# mbeduino010_eagle6.net
KiCad netlist of a schematic drawn in EAGLE
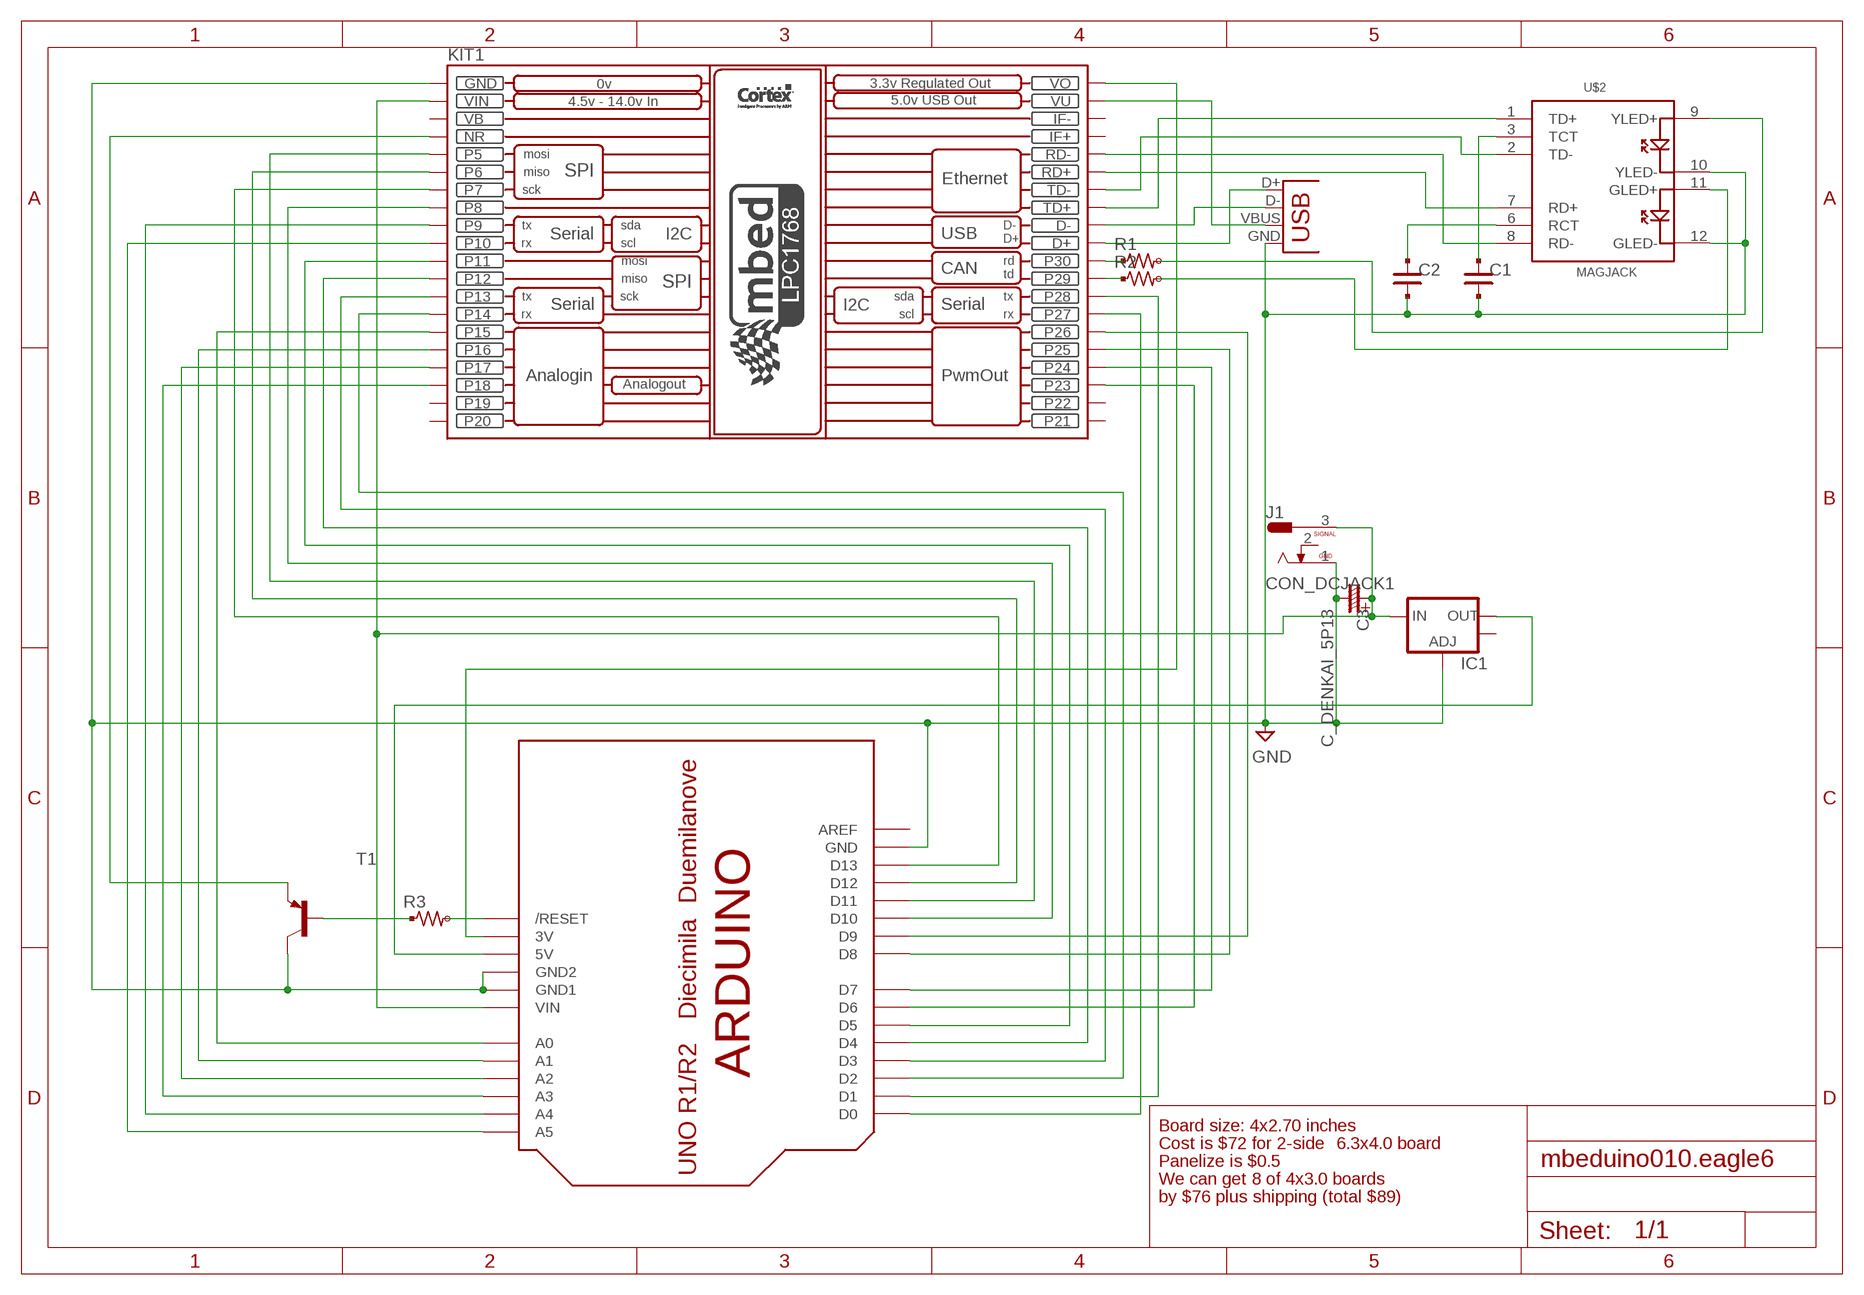
[diagram p0: schematic, sheet 1]

(export (version "E")
  (design (tool "Eeschema 10.0.6"))
  (components
    (comp (ref "C1")
      (value "C_PAD_PAD_2125")
      (footprint "eagle-import:CR_2125")
      (libsource (lib "eagle-import") (part "C_PAD_PAD_2125"))
    )
    (comp (ref "C2")
      (value "C_PAD_PAD_2125")
      (footprint "eagle-import:CR_2125")
      (libsource (lib "eagle-import") (part "C_PAD_PAD_2125"))
    )
    (comp (ref "C3")
      (value "C_DENKAI_5P13")
      (footprint "eagle-import:C_2.5PHI6")
      (libsource (lib "eagle-import") (part "C_DENKAI_2.5P6"))
    )
    (comp (ref "IC1")
      (value "V_REG_LM1117SOT223")
      (footprint "eagle-import:SOT223")
      (libsource (lib "eagle-import") (part "V_REG_LM1117SOT223"))
    )
    (comp (ref "J1")
      (value "CON_DCJACK1")
      (footprint "eagle-import:CON_DCJACK")
      (libsource (lib "eagle-import") (part "CON_DCJACK1"))
    )
    (comp (ref "KIT1")
      (value "MBED_NXP_LPC1768")
      (footprint "eagle-import:MBED-KIT")
      (libsource (lib "eagle-import") (part "MBED_NXP_LPC1768"))
    )
    (comp (ref "R1")
      (value "R_US_PAD_VIA_2125")
      (footprint "eagle-import:R_2125_PADVIA")
      (libsource (lib "eagle-import") (part "R_US_PAD_VIA_2125"))
    )
    (comp (ref "R2")
      (value "R_US_PAD_VIA_2125")
      (footprint "eagle-import:R_2125_PADVIA")
      (libsource (lib "eagle-import") (part "R_US_PAD_VIA_2125"))
    )
    (comp (ref "R3")
      (value "R_US_PAD_VIA_2125")
      (footprint "eagle-import:R_2125_PADVIA")
      (libsource (lib "eagle-import") (part "R_US_PAD_VIA_2125"))
    )
    (comp (ref "T1")
      (value "-PNP-SOT23-BCE")
      (footprint "eagle-import:SOT23-BCE")
      (libsource (lib "eagle-import") (part "-PNP-SOT23-BCE"))
    )
    (comp (ref "U$1")
      (value "ARDUINO-NOHOLE")
      (footprint "eagle-import:ARDUINO-NOHOLE")
      (libsource (lib "eagle-import") (part "ARDUINO-NOHOLE"))
    )
    (comp (ref "U$2")
      (value "MAGJACK")
      (footprint "eagle-import:MAGJACK")
      (libsource (lib "eagle-import") (part "MAGJACK"))
    )
    (comp (ref "X1")
      (value "USB-A-S")
      (footprint "eagle-import:USB-A-S")
      (libsource (lib "eagle-import") (part "USB-A-S"))
    )
  )
  (nets
    (net (code "1") (name "/VB") (class "Default")
      (node (ref "KIT1") (pin "VB") (pinfunction "VB_VB") (pintype "power_in"))
    )
    (net (code "2") (name "GND") (class "Default")
      (node (ref "C1") (pin "2") (pinfunction "2_2") (pintype "passive"))
      (node (ref "C2") (pin "2") (pinfunction "2_2") (pintype "passive"))
      (node (ref "C3") (pin "-") (pinfunction "-_-") (pintype "passive"))
      (node (ref "IC1") (pin "1") (pinfunction "ADJ_1") (pintype "input"))
      (node (ref "J1") (pin "1") (pinfunction "3_1") (pintype "passive"))
      (node (ref "KIT1") (pin "GND") (pinfunction "GND_GND") (pintype "power_in"))
      (node (ref "T1") (pin "C") (pinfunction "C_C") (pintype "passive"))
      (node (ref "U$1") (pin "GND") (pinfunction "GND_GND") (pintype "power_in"))
      (node (ref "U$1") (pin "GND1") (pinfunction "GND1_GND1") (pintype "power_in"))
      (node (ref "U$1") (pin "GND2") (pinfunction "GND2_GND2") (pintype "power_in"))
      (node (ref "U$2") (pin "10") (pinfunction "YLED-_10") (pintype "bidirectional"))
      (node (ref "U$2") (pin "12") (pinfunction "GLED-_12") (pintype "bidirectional"))
      (node (ref "X1") (pin "GND") (pinfunction "GND_GND") (pintype "bidirectional"))
    )
    (net (code "3") (name "Net-(IC1-IN)") (class "Default")
      (node (ref "C3") (pin "+") (pinfunction "+_+") (pintype "passive"))
      (node (ref "IC1") (pin "3") (pinfunction "IN_3") (pintype "input"))
      (node (ref "J1") (pin "3") (pinfunction "1_3") (pintype "passive"))
      (node (ref "KIT1") (pin "VIN") (pinfunction "VIN_VIN") (pintype "power_in"))
      (node (ref "U$1") (pin "VIN") (pinfunction "VIN_VIN") (pintype "power_in"))
    )
    (net (code "4") (name "Net-(IC1-OUT-Pad2)") (class "Default")
      (node (ref "IC1") (pin "2") (pinfunction "OUT_2") (pintype "output"))
      (node (ref "U$1") (pin "5V") (pinfunction "5V_5V") (pintype "power_in"))
    )
    (net (code "5") (name "Net-(KIT1-P5)") (class "Default")
      (node (ref "KIT1") (pin "P$5") (pinfunction "P5_P$5") (pintype "bidirectional"))
      (node (ref "U$1") (pin "D11") (pinfunction "D11_D11") (pintype "bidirectional"))
    )
    (net (code "6") (name "Net-(KIT1-P6)") (class "Default")
      (node (ref "KIT1") (pin "P$6") (pinfunction "P6_P$6") (pintype "bidirectional"))
      (node (ref "U$1") (pin "D12") (pinfunction "D12_D12") (pintype "bidirectional"))
    )
    (net (code "7") (name "Net-(KIT1-P7)") (class "Default")
      (node (ref "KIT1") (pin "P$7") (pinfunction "P7_P$7") (pintype "bidirectional"))
      (node (ref "U$1") (pin "D13") (pinfunction "D13_D13") (pintype "bidirectional"))
    )
    (net (code "8") (name "Net-(KIT1-P8)") (class "Default")
      (node (ref "KIT1") (pin "P$8") (pinfunction "P8_P$8") (pintype "bidirectional"))
      (node (ref "U$1") (pin "D10") (pinfunction "D10_D10") (pintype "bidirectional"))
    )
    (net (code "9") (name "Net-(KIT1-P9)") (class "Default")
      (node (ref "KIT1") (pin "P$9") (pinfunction "P9_P$9") (pintype "bidirectional"))
      (node (ref "U$1") (pin "A4") (pinfunction "A4_A4") (pintype "bidirectional"))
    )
    (net (code "10") (name "Net-(KIT1-P10)") (class "Default")
      (node (ref "KIT1") (pin "P$10") (pinfunction "P10_P$10") (pintype "bidirectional"))
      (node (ref "U$1") (pin "A5") (pinfunction "A5_A5") (pintype "bidirectional"))
    )
    (net (code "11") (name "Net-(KIT1-P11)") (class "Default")
      (node (ref "KIT1") (pin "P$11") (pinfunction "P11_P$11") (pintype "bidirectional"))
      (node (ref "U$1") (pin "D5") (pinfunction "D5_D5") (pintype "bidirectional"))
    )
    (net (code "12") (name "Net-(KIT1-P12)") (class "Default")
      (node (ref "KIT1") (pin "P$12") (pinfunction "P12_P$12") (pintype "bidirectional"))
      (node (ref "U$1") (pin "D4") (pinfunction "D4_D4") (pintype "bidirectional"))
    )
    (net (code "13") (name "Net-(KIT1-P13)") (class "Default")
      (node (ref "KIT1") (pin "P$13") (pinfunction "P13_P$13") (pintype "bidirectional"))
      (node (ref "U$1") (pin "D3") (pinfunction "D3_D3") (pintype "bidirectional"))
    )
    (net (code "14") (name "Net-(KIT1-P14)") (class "Default")
      (node (ref "KIT1") (pin "P$14") (pinfunction "P14_P$14") (pintype "bidirectional"))
      (node (ref "U$1") (pin "D2") (pinfunction "D2_D2") (pintype "bidirectional"))
    )
    (net (code "15") (name "Net-(KIT1-P15)") (class "Default")
      (node (ref "KIT1") (pin "P$15") (pinfunction "P15_P$15") (pintype "bidirectional"))
      (node (ref "U$1") (pin "A0") (pinfunction "A0_A0") (pintype "bidirectional"))
    )
    (net (code "16") (name "Net-(KIT1-P16)") (class "Default")
      (node (ref "KIT1") (pin "P$16") (pinfunction "P16_P$16") (pintype "bidirectional"))
      (node (ref "U$1") (pin "A1") (pinfunction "A1_A1") (pintype "bidirectional"))
    )
    (net (code "17") (name "Net-(KIT1-P17)") (class "Default")
      (node (ref "KIT1") (pin "P$17") (pinfunction "P17_P$17") (pintype "bidirectional"))
      (node (ref "U$1") (pin "A2") (pinfunction "A2_A2") (pintype "bidirectional"))
    )
    (net (code "18") (name "Net-(KIT1-P18)") (class "Default")
      (node (ref "KIT1") (pin "P$18") (pinfunction "P18_P$18") (pintype "bidirectional"))
      (node (ref "U$1") (pin "A3") (pinfunction "A3_A3") (pintype "bidirectional"))
    )
    (net (code "19") (name "Net-(KIT1-P23)") (class "Default")
      (node (ref "KIT1") (pin "P$23") (pinfunction "P23_P$23") (pintype "bidirectional"))
      (node (ref "U$1") (pin "D6") (pinfunction "D6_D6") (pintype "bidirectional"))
    )
    (net (code "20") (name "Net-(KIT1-P24)") (class "Default")
      (node (ref "KIT1") (pin "P$24") (pinfunction "P24_P$24") (pintype "bidirectional"))
      (node (ref "U$1") (pin "D7") (pinfunction "D7_D7") (pintype "bidirectional"))
    )
    (net (code "21") (name "Net-(KIT1-P25)") (class "Default")
      (node (ref "KIT1") (pin "P$25") (pinfunction "P25_P$25") (pintype "bidirectional"))
      (node (ref "U$1") (pin "D8") (pinfunction "D8_D8") (pintype "bidirectional"))
    )
    (net (code "22") (name "Net-(KIT1-P26)") (class "Default")
      (node (ref "KIT1") (pin "P$26") (pinfunction "P26_P$26") (pintype "bidirectional"))
      (node (ref "U$1") (pin "D9") (pinfunction "D9_D9") (pintype "bidirectional"))
    )
    (net (code "23") (name "Net-(KIT1-P27)") (class "Default")
      (node (ref "KIT1") (pin "P$27") (pinfunction "P27_P$27") (pintype "bidirectional"))
      (node (ref "U$1") (pin "D0") (pinfunction "D0_D0") (pintype "bidirectional"))
    )
    (net (code "24") (name "Net-(KIT1-P28)") (class "Default")
      (node (ref "KIT1") (pin "P$28") (pinfunction "P28_P$28") (pintype "bidirectional"))
      (node (ref "U$1") (pin "D1") (pinfunction "D1_D1") (pintype "bidirectional"))
    )
    (net (code "25") (name "Net-(KIT1-P29)") (class "Default")
      (node (ref "KIT1") (pin "P$29") (pinfunction "P29_P$29") (pintype "bidirectional"))
      (node (ref "R2") (pin "PAD") (pinfunction "PAD_PAD") (pintype "passive"))
    )
    (net (code "26") (name "Net-(KIT1-P30)") (class "Default")
      (node (ref "KIT1") (pin "P$30") (pinfunction "P30_P$30") (pintype "bidirectional"))
      (node (ref "R1") (pin "PAD") (pinfunction "PAD_PAD") (pintype "passive"))
    )
    (net (code "27") (name "Net-(KIT1-PadD+)") (class "Default")
      (node (ref "KIT1") (pin "D+") (pinfunction "D+_D+") (pintype "bidirectional"))
      (node (ref "X1") (pin "D+") (pinfunction "D+_D+") (pintype "bidirectional"))
    )
    (net (code "28") (name "Net-(KIT1-PadD-)") (class "Default")
      (node (ref "KIT1") (pin "D-") (pinfunction "D-_D-") (pintype "bidirectional"))
      (node (ref "X1") (pin "D-") (pinfunction "D-_D-") (pintype "bidirectional"))
    )
    (net (code "29") (name "Net-(KIT1-PadNR)") (class "Default")
      (node (ref "KIT1") (pin "NR") (pinfunction "NR_NR") (pintype "power_in"))
      (node (ref "T1") (pin "E") (pinfunction "E_E") (pintype "passive"))
    )
    (net (code "30") (name "Net-(KIT1-PadVU)") (class "Default")
      (node (ref "KIT1") (pin "VU") (pinfunction "VU_VU") (pintype "power_in"))
      (node (ref "X1") (pin "VBUS") (pinfunction "VBUS_VBUS") (pintype "bidirectional"))
    )
    (net (code "31") (name "Net-(KIT1-VO)") (class "Default")
      (node (ref "KIT1") (pin "VOUT") (pinfunction "VO_VOUT") (pintype "power_in"))
      (node (ref "U$1") (pin "3V") (pinfunction "3V_3V") (pintype "power_in"))
    )
    (net (code "32") (name "Net-(R3-PadPAD)") (class "Default")
      (node (ref "R3") (pin "PAD") (pinfunction "PAD_PAD") (pintype "passive"))
      (node (ref "T1") (pin "B") (pinfunction "B_B") (pintype "passive"))
    )
    (net (code "33") (name "Net-(U$1-{slash}RESET)") (class "Default")
      (node (ref "R3") (pin "VIA") (pinfunction "VIA_VIA") (pintype "passive"))
      (node (ref "U$1") (pin "RESET") (pinfunction "/RESET_RESET") (pintype "bidirectional"))
    )
    (net (code "34") (name "Net-(U$2-GLED+)") (class "Default")
      (node (ref "R2") (pin "VIA") (pinfunction "VIA_VIA") (pintype "passive"))
      (node (ref "U$2") (pin "11") (pinfunction "GLED+_11") (pintype "bidirectional"))
    )
    (net (code "35") (name "Net-(U$2-RCT)") (class "Default")
      (node (ref "C2") (pin "1") (pinfunction "1_1") (pintype "passive"))
      (node (ref "U$2") (pin "6") (pinfunction "RCT_6") (pintype "bidirectional"))
    )
    (net (code "36") (name "Net-(U$2-RD+)") (class "Default")
      (node (ref "KIT1") (pin "RD+") (pinfunction "RD+_RD+") (pintype "bidirectional"))
      (node (ref "U$2") (pin "7") (pinfunction "RD+_7") (pintype "bidirectional"))
    )
    (net (code "37") (name "Net-(U$2-RD-)") (class "Default")
      (node (ref "KIT1") (pin "RD-") (pinfunction "RD-_RD-") (pintype "bidirectional"))
      (node (ref "U$2") (pin "8") (pinfunction "RD-_8") (pintype "bidirectional"))
    )
    (net (code "38") (name "Net-(U$2-TCT)") (class "Default")
      (node (ref "C1") (pin "1") (pinfunction "1_1") (pintype "passive"))
      (node (ref "U$2") (pin "3") (pinfunction "TCT_3") (pintype "bidirectional"))
    )
    (net (code "39") (name "Net-(U$2-TD+)") (class "Default")
      (node (ref "KIT1") (pin "TD+") (pinfunction "TD+_TD+") (pintype "bidirectional"))
      (node (ref "U$2") (pin "1") (pinfunction "TD+_1") (pintype "bidirectional"))
    )
    (net (code "40") (name "Net-(U$2-TD-)") (class "Default")
      (node (ref "KIT1") (pin "TD-") (pinfunction "TD-_TD-") (pintype "bidirectional"))
      (node (ref "U$2") (pin "2") (pinfunction "TD-_2") (pintype "bidirectional"))
    )
    (net (code "41") (name "Net-(U$2-YLED+)") (class "Default")
      (node (ref "R1") (pin "VIA") (pinfunction "VIA_VIA") (pintype "passive"))
      (node (ref "U$2") (pin "9") (pinfunction "YLED+_9") (pintype "bidirectional"))
    )
    (net (code "42") (name "unconnected-(IC1-OUT-Pad4)") (class "Default")
      (node (ref "IC1") (pin "4") (pinfunction "OUT_4") (pintype "output"))
    )
    (net (code "43") (name "unconnected-(J1-Pad2)") (class "Default")
      (node (ref "J1") (pin "2") (pinfunction "2_2") (pintype "passive"))
    )
    (net (code "44") (name "unconnected-(KIT1-P19-PadP$19)") (class "Default")
      (node (ref "KIT1") (pin "P$19") (pinfunction "P19_P$19") (pintype "bidirectional"))
    )
    (net (code "45") (name "unconnected-(KIT1-P20-PadP$20)") (class "Default")
      (node (ref "KIT1") (pin "P$20") (pinfunction "P20_P$20") (pintype "bidirectional"))
    )
    (net (code "46") (name "unconnected-(KIT1-P21-PadP$21)") (class "Default")
      (node (ref "KIT1") (pin "P$21") (pinfunction "P21_P$21") (pintype "bidirectional"))
    )
    (net (code "47") (name "unconnected-(KIT1-P22-PadP$22)") (class "Default")
      (node (ref "KIT1") (pin "P$22") (pinfunction "P22_P$22") (pintype "bidirectional"))
    )
    (net (code "48") (name "unconnected-(KIT1-PadIF+)") (class "Default")
      (node (ref "KIT1") (pin "IF+") (pinfunction "IF+_IF+") (pintype "bidirectional"))
    )
    (net (code "49") (name "unconnected-(KIT1-PadIF-)") (class "Default")
      (node (ref "KIT1") (pin "IF-") (pinfunction "IF-_IF-") (pintype "bidirectional"))
    )
    (net (code "50") (name "unconnected-(U$1-PadAREF)") (class "Default")
      (node (ref "U$1") (pin "AREF") (pinfunction "AREF_AREF") (pintype "bidirectional"))
    )
  )
)
